# Kick_Sheet.net
KiCad netlist of a schematic drawn in Altium Designer
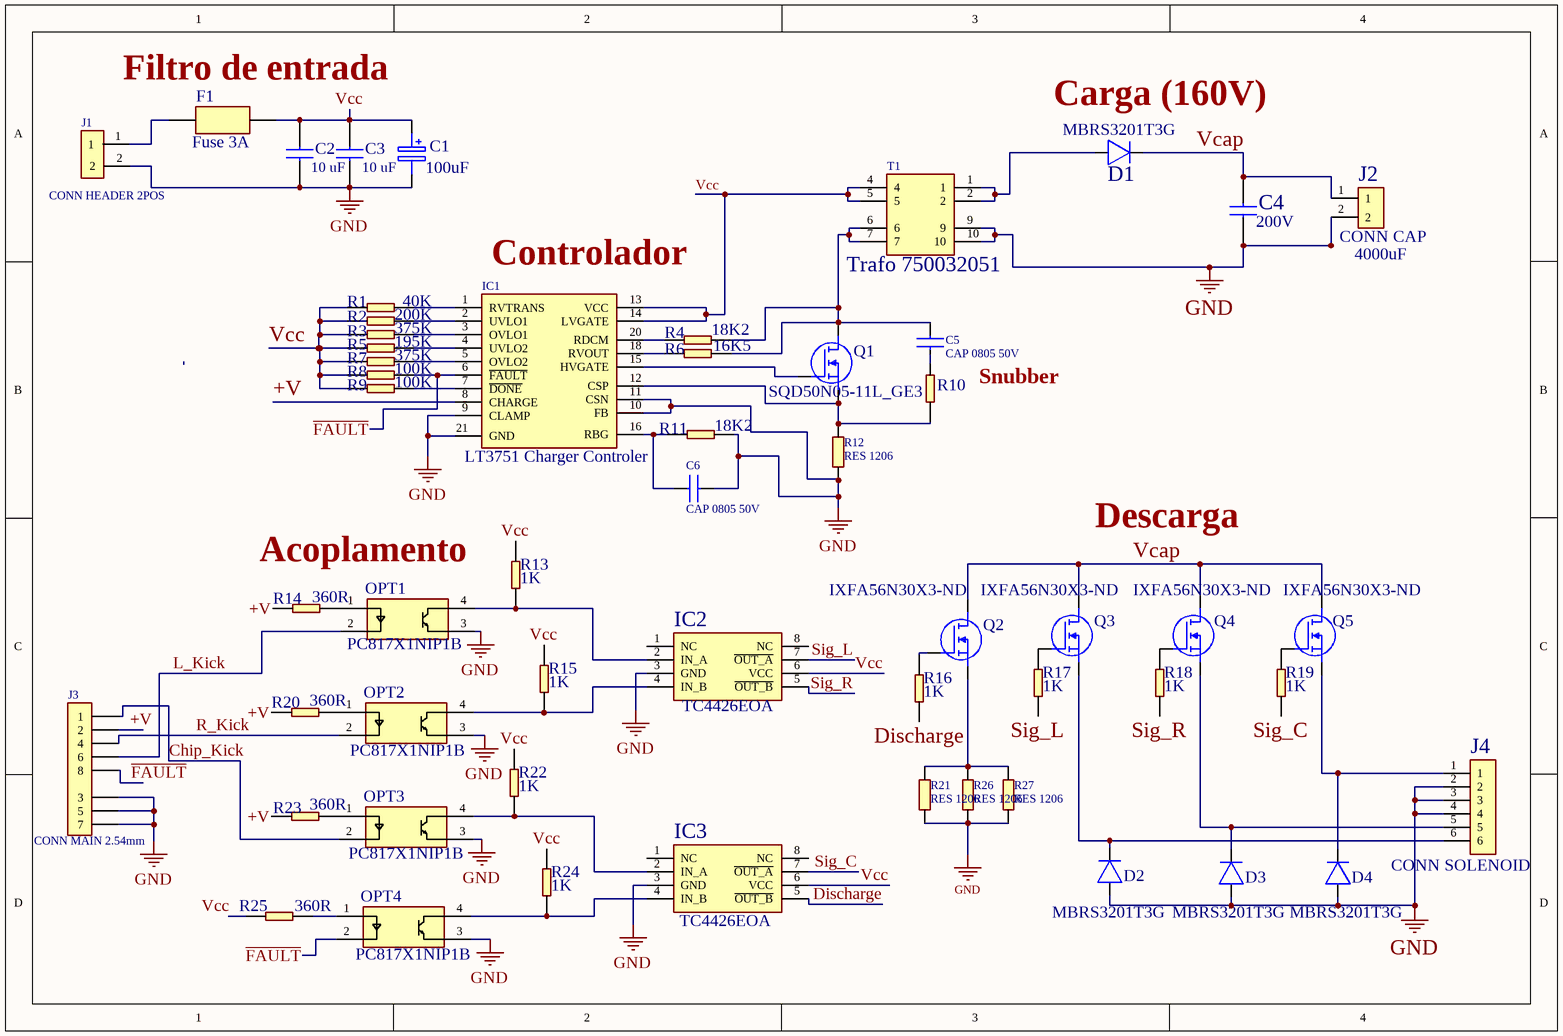
[diagram p0: Kick_Sheet.SchDoc]

(export (version "E")
  (design (tool "Eeschema 10.0.6"))
  (components
    (comp (ref "C1")
      (value "100uF")
      (footprint "SamacSys:CAPAE830X1050N")
      (fields
        (field (name "MANUFACTURER_PART_NUMBER") "UCD1H101MNL1GS")
        (field (name "MOUSER PART NUMBER") "647-UCD1H101MNL1GS")
        (field (name "RS PART NUMBER") "7151372P")
      )
      (libsource (lib "LIB_SCH_Kick") (part "CAP ALUM 100UF 20% 50V SMD"))
    )
    (comp (ref "C2")
      (value "10 uF")
      (footprint "PcbLib1:CAPCER1206")
      (description "Capacitor C3216C0G1H103J060AA")
      (fields
        (field (name "MANUFACTURER_PART_NUMBER") "C3216C0G1H103J060AA")
        (field (name "MOUSER PART NUMBER") "810-C3216C0G1H103J-1")
      )
      (libsource (lib "Schlib1") (part "CAP CER 1206"))
    )
    (comp (ref "C3")
      (value "10 uF")
      (footprint "PcbLib1:CAPCER1206")
      (description "Capacitor C3216C0G1H103J060AA")
      (fields
        (field (name "MANUFACTURER_PART_NUMBER") "C3216C0G1H103J060AA")
        (field (name "MOUSER PART NUMBER") "810-C3216C0G1H103J-1")
      )
      (libsource (lib "Schlib1") (part "CAP CER 1206"))
    )
    (comp (ref "C4")
      (value "200V")
      (footprint "PcbLib1:CAP OUT 2225")
      (description "Capacitor\r\nCAP CER 1UF 200V X7R 2225\r\n720-1136-1-ND\r\nVJ2225Y105KXCAT")
      (fields
        (field (name "MANUFACTURER_PART_NUMBER") "2225HC103KAZ1A")
        (field (name "MOUSER PART NUMBER") "581-2225HC103KAZ1A")
      )
      (libsource (lib "Schlib1") (part "CAP OUT 2225"))
    )
    (comp (ref "C5")
      (value "CAP 0805 50V")
      (footprint "LIB_PCB_Kick:CAP0805 50v")
      (description "Capacitor\r\n08055A101JAT2A")
      (fields
        (field (name "MANUFACTURER_PART_NUMBER") "08055A101JAT2A")
        (field (name "MOUSER PART NUMBER") "581-08055A101J")
      )
      (libsource (lib "LIB_SCH_Kick") (part "CAP 0805 50V"))
    )
    (comp (ref "C6")
      (value "CAP 0805 50V")
      (footprint "LIB_PCB_Kick:CAP0805 50v")
      (description "Capacitor\r\n08055A101JAT2A")
      (fields
        (field (name "MANUFACTURER_PART_NUMBER") "08055A101JAT2A")
        (field (name "MOUSER PART NUMBER") "581-08055A101J")
      )
      (libsource (lib "LIB_SCH_Kick") (part "CAP 0805 50V"))
    )
    (comp (ref "D1")
      (value "MBRS3201T3G")
      (footprint "PcbLib1:DIODE MBRS3201T")
      (description "Diode\r\nMBRS3201T3G")
      (fields
        (field (name "MOUSER PART NUMBER") "863-MBRS3201T3G")
        (field (name "RS PART NUMBER") "7925640P")
      )
      (libsource (lib "Schlib1") (part "DIODE MBRS3201T3G"))
    )
    (comp (ref "D2")
      (value "MBRS3201T3G")
      (footprint "PcbLib1:DIODE MBRS3201T")
      (description "Diode\r\nMBRS3201T3G")
      (fields
        (field (name "MOUSER PART NUMBER") "863-MBRS3201T3G")
        (field (name "RS PART NUMBER") "7925640P")
      )
      (libsource (lib "Schlib1") (part "DIODE MBRS3201T3G"))
    )
    (comp (ref "D3")
      (value "MBRS3201T3G")
      (footprint "PcbLib1:DIODE MBRS3201T")
      (description "Diode\r\nMBRS3201T3G")
      (fields
        (field (name "MOUSER PART NUMBER") "863-MBRS3201T3G")
        (field (name "RS PART NUMBER") "7925640P")
      )
      (libsource (lib "Schlib1") (part "DIODE MBRS3201T3G"))
    )
    (comp (ref "D4")
      (value "MBRS3201T3G")
      (footprint "PcbLib1:DIODE MBRS3201T")
      (description "Diode\r\nMBRS3201T3G")
      (fields
        (field (name "MOUSER PART NUMBER") "863-MBRS3201T3G")
        (field (name "RS PART NUMBER") "7925640P")
      )
      (libsource (lib "Schlib1") (part "DIODE MBRS3201T3G"))
    )
    (comp (ref "F1")
      (value "Fuse 3A")
      (footprint "PcbLib1:Fuse 3A 63V")
      (description "Fuse\r\nFUSE 3.0A 63VAC/DC SLOW 1206\r\n507-1896-1-ND\r\n0685T3000-01")
      (fields
        (field (name "MANUFACTURER_PART_NUMBER") "0466001.NRHF")
        (field (name "MOUSER PART NUMBER") "576-0466001.NRHF")
      )
      (libsource (lib "Schlib1") (part "Fuse 3A 63V"))
    )
    (comp (ref "IC1")
      (value "LT3751 Charger Controler")
      (footprint "PcbLib1:LT3751 Charger Controler")
      (description "Integrated Circuit")
      (fields (field (name "MANUFACTURER_PART_NUMBER") "LT3751EFEPBF"))
      (libsource (lib "Schlib1") (part "LT3751 Charger Controler"))
    )
    (comp (ref "IC2")
      (value "TC4426EOA")
      (footprint "PcbLib1:SOIC127_TC4426")
      (description "Integrated Circuit")
      (fields (field (name "MOUSER PART NUMBER") "579-TC4426EOA") (field (name "RS PART NUMBER") "6684345"))
      (libsource (lib "Schlib1") (part "TC4426EOA"))
    )
    (comp (ref "IC3")
      (value "TC4426EOA")
      (footprint "PcbLib1:SOIC127_TC4426")
      (description "Integrated Circuit")
      (fields (field (name "MOUSER PART NUMBER") "579-TC4426EOA") (field (name "RS PART NUMBER") "6684345"))
      (libsource (lib "Schlib1") (part "TC4426EOA"))
    )
    (comp (ref "J1")
      (value "CONN HEADER 2POS")
      (footprint "LIB_PCB_Kick:Battery Reto Connector")
      (description "CONN HEADER R/A 2POS 2.54MM\r\n22-05-3021\r\nWM4300-ND")
      (fields
        (field (name "MANUFACTURER_PART_NUMBER") "22-05-3021")
        (field (name "MOUSER PART NUMBER") "538-22-05-3021")
      )
      (libsource (lib "LIB_SCH_Kick") (part "Battery Connector"))
    )
    (comp (ref "J2")
      (value "CONN CAP")
      (footprint "PcbLib1:CONN CAP")
      (description "Connector\r\nCONN HEADER VERT 2POS 3.96MM\r\n0009652028\r\nWM18823-ND")
      (fields
        (field (name "MANUFACTURER_PART_NUMBER") "09-65-2028")
        (field (name "MOUSER PART NUMBER") "538-09-65-2028")
        (field (name "CAPACITANCIA") "4000uF")
      )
      (libsource (lib "Schlib1") (part "CONN CAP"))
    )
    (comp (ref "J3")
      (value "CONN MAIN 2.54mm")
      (footprint "LIB_PCB_Kick:CONN MAIN 2.54mm")
      (description "Connector\r\n\r\nCONN HEADER VERT 8POS 2.54MM\r\n\r\nM20-9980445\r\n\r\n952-2122-ND")
      (fields
        (field (name "MANUFACTURER_PART_NUMBER") "20021311-00010T4LF")
        (field (name "MOUSER PART NUMBER") "649-221311-00010T4LF")
      )
      (libsource (lib "LIB_SCH_Kick") (part "CONN MAIN 2.54mm"))
    )
    (comp (ref "J4")
      (value "CONN SOLENOID")
      (footprint "PcbLib1:CONN SOLENOID")
      (description "Connector\r\nCONN HEADER VERT 6POS 3.96MM\r\n0026604060\r\nWM4624-ND")
      (fields
        (field (name "MANUFACTURER_PART_NUMBER") "640445-6")
        (field (name "MOUSER PART NUMBER") "571-6404456")
      )
      (libsource (lib "Schlib1") (part "CONN SOLENOID"))
    )
    (comp (ref "OPT1")
      (value "PC817X1NIP1B")
      (footprint "PcbLib1:SOP254_Opto_PC817")
      (description "Integrated Circuit")
      (fields (field (name "MOUSER PART NUMBER") "852-PC817X1NIP1B"))
      (libsource (lib "Schlib1") (part "PC817X1NIP1B"))
    )
    (comp (ref "OPT2")
      (value "PC817X1NIP1B")
      (footprint "PcbLib1:SOP254_Opto_PC817")
      (description "Integrated Circuit")
      (fields (field (name "MOUSER PART NUMBER") "852-PC817X1NIP1B"))
      (libsource (lib "Schlib1") (part "PC817X1NIP1B"))
    )
    (comp (ref "OPT3")
      (value "PC817X1NIP1B")
      (footprint "PcbLib1:SOP254_Opto_PC817")
      (description "Integrated Circuit")
      (fields (field (name "MOUSER PART NUMBER") "852-PC817X1NIP1B"))
      (libsource (lib "Schlib1") (part "PC817X1NIP1B"))
    )
    (comp (ref "OPT4")
      (value "PC817X1NIP1B")
      (footprint "PcbLib1:SOP254_Opto_PC817")
      (description "Integrated Circuit")
      (fields (field (name "MOUSER PART NUMBER") "852-PC817X1NIP1B"))
      (libsource (lib "Schlib1") (part "PC817X1NIP1B"))
    )
    (comp (ref "Q1")
      (value "Mosfet N 50V 50A")
      (footprint "PcbLib1:Mosfet Chaveamento")
      (fields (field (name "MANUFACTURER_PART_NUMBER") "SQD50N05-11L_GE3"))
      (libsource (lib "Schlib1") (part "Mosfet Chaveamento"))
    )
    (comp (ref "Q2")
      (value "Mosfet N Disparo")
      (footprint "PcbLib1:Mosfet Disparo 2")
      (fields (field (name "MANUFACTURER_PART_NUMBER") "IXFA56N30X3-ND"))
      (libsource (lib "Schlib1") (part "Mosfet N Disparo"))
    )
    (comp (ref "Q3")
      (value "Mosfet N Disparo")
      (footprint "PcbLib1:Mosfet Disparo 2")
      (fields (field (name "MANUFACTURER_PART_NUMBER") "IXFA56N30X3-ND"))
      (libsource (lib "Schlib1") (part "Mosfet N Disparo"))
    )
    (comp (ref "Q4")
      (value "Mosfet N Disparo")
      (footprint "PcbLib1:Mosfet Disparo 2")
      (fields (field (name "MANUFACTURER_PART_NUMBER") "IXFA56N30X3-ND"))
      (libsource (lib "Schlib1") (part "Mosfet N Disparo"))
    )
    (comp (ref "Q5")
      (value "Mosfet N Disparo")
      (footprint "PcbLib1:Mosfet Disparo 2")
      (fields (field (name "MANUFACTURER_PART_NUMBER") "IXFA56N30X3-ND"))
      (libsource (lib "Schlib1") (part "Mosfet N Disparo"))
    )
    (comp (ref "R1")
      (value "40K")
      (footprint "PcbLib1:RES 0805")
      (description "Resistor 0805")
      (fields
        (field (name "MANUFACTURER_PART_NUMBER") "CPF0805B105RE1")
        (field (name "MOUSER PART NUMBER") "279-CPF0805B105RE1")
      )
      (libsource (lib "") (part "Resistor 0805_1"))
    )
    (comp (ref "R2")
      (value "200K")
      (footprint "PcbLib1:RES 0805")
      (description "Resistor 0805")
      (fields
        (field (name "MANUFACTURER_PART_NUMBER") "CPF0805B105RE1")
        (field (name "MOUSER PART NUMBER") "279-CPF0805B105RE1")
      )
      (libsource (lib "") (part "Resistor 0805_1"))
    )
    (comp (ref "R3")
      (value "375K")
      (footprint "PcbLib1:RES 0805")
      (description "Resistor 0805")
      (fields
        (field (name "MANUFACTURER_PART_NUMBER") "CPF0805B105RE1")
        (field (name "MOUSER PART NUMBER") "279-CPF0805B105RE1")
      )
      (libsource (lib "") (part "Resistor 0805_1"))
    )
    (comp (ref "R4")
      (value "18K2")
      (footprint "PcbLib1:RES 0805")
      (description "Resistor 0805")
      (fields
        (field (name "MANUFACTURER_PART_NUMBER") "CPF0805B105RE1")
        (field (name "MOUSER PART NUMBER") "279-CPF0805B105RE1")
      )
      (libsource (lib "") (part "Resistor 0805_1"))
    )
    (comp (ref "R5")
      (value "195K")
      (footprint "PcbLib1:RES 0805")
      (description "Resistor 0805")
      (fields
        (field (name "MANUFACTURER_PART_NUMBER") "CPF0805B105RE1")
        (field (name "MOUSER PART NUMBER") "279-CPF0805B105RE1")
      )
      (libsource (lib "") (part "Resistor 0805_1"))
    )
    (comp (ref "R6")
      (value "16K5")
      (footprint "PcbLib1:RES 0805")
      (description "Resistor 0805")
      (fields
        (field (name "MANUFACTURER_PART_NUMBER") "CPF0805B105RE1")
        (field (name "MOUSER PART NUMBER") "279-CPF0805B105RE1")
      )
      (libsource (lib "") (part "Resistor 0805_1"))
    )
    (comp (ref "R7")
      (value "375K")
      (footprint "PcbLib1:RES 0805")
      (description "Resistor 0805")
      (fields
        (field (name "MANUFACTURER_PART_NUMBER") "CPF0805B105RE1")
        (field (name "MOUSER PART NUMBER") "279-CPF0805B105RE1")
      )
      (libsource (lib "") (part "Resistor 0805_1"))
    )
    (comp (ref "R8")
      (value "100K")
      (footprint "PcbLib1:RES 0805")
      (description "Resistor 0805")
      (fields
        (field (name "MANUFACTURER_PART_NUMBER") "CPF0805B105RE1")
        (field (name "MOUSER PART NUMBER") "279-CPF0805B105RE1")
      )
      (libsource (lib "") (part "Resistor 0805_1"))
    )
    (comp (ref "R9")
      (value "100K")
      (footprint "PcbLib1:RES 0805")
      (description "Resistor 0805")
      (fields
        (field (name "MANUFACTURER_PART_NUMBER") "CPF0805B105RE1")
        (field (name "MOUSER PART NUMBER") "279-CPF0805B105RE1")
      )
      (libsource (lib "") (part "Resistor 0805_1"))
    )
    (comp (ref "R10")
      (value "~")
      (footprint "PcbLib1:RES 0805")
      (description "Resistor 0805")
      (fields
        (field (name "MANUFACTURER_PART_NUMBER") "CPF0805B105RE1")
        (field (name "MOUSER PART NUMBER") "279-CPF0805B105RE1")
      )
      (libsource (lib "Schlib1") (part "Resistor 0805"))
    )
    (comp (ref "R11")
      (value "18K2")
      (footprint "PcbLib1:RES 0805")
      (description "Resistor 0805")
      (fields
        (field (name "MANUFACTURER_PART_NUMBER") "CPF0805B105RE1")
        (field (name "MOUSER PART NUMBER") "279-CPF0805B105RE1")
      )
      (libsource (lib "") (part "Resistor 0805_1"))
    )
    (comp (ref "R12")
      (value "RES 1206")
      (footprint "LIB_PCB_Kick:Res 1206")
      (description "Resistor CR1206-FW-1504ELF")
      (fields
        (field (name "MANUFACTURER_PART_NUMBER") "CR1206-FW-1504ELF")
        (field (name "MOUSER PART NUMBER") "652-CR1206FW1504ELF")
      )
      (libsource (lib "") (part "RES 1206_1"))
    )
    (comp (ref "R13")
      (value "1K")
      (footprint "PcbLib1:RES 0805")
      (description "Resistor 0805")
      (fields
        (field (name "MANUFACTURER_PART_NUMBER") "CPF0805B105RE1")
        (field (name "MOUSER PART NUMBER") "279-CPF0805B105RE1")
      )
      (libsource (lib "Schlib1") (part "Resistor 0805"))
    )
    (comp (ref "R14")
      (value "360R")
      (footprint "PcbLib1:RES 0805")
      (description "Resistor 0805")
      (fields
        (field (name "MANUFACTURER_PART_NUMBER") "CPF0805B105RE1")
        (field (name "MOUSER PART NUMBER") "279-CPF0805B105RE1")
      )
      (libsource (lib "") (part "Resistor 0805_1"))
    )
    (comp (ref "R15")
      (value "1K")
      (footprint "PcbLib1:RES 0805")
      (description "Resistor 0805")
      (fields
        (field (name "MANUFACTURER_PART_NUMBER") "CPF0805B105RE1")
        (field (name "MOUSER PART NUMBER") "279-CPF0805B105RE1")
      )
      (libsource (lib "Schlib1") (part "Resistor 0805"))
    )
    (comp (ref "R16")
      (value "1K")
      (footprint "PcbLib1:RES 0805")
      (description "Resistor 0805")
      (fields
        (field (name "MANUFACTURER_PART_NUMBER") "CPF0805B105RE1")
        (field (name "MOUSER PART NUMBER") "279-CPF0805B105RE1")
      )
      (libsource (lib "Schlib1") (part "Resistor 0805"))
    )
    (comp (ref "R17")
      (value "1K")
      (footprint "PcbLib1:RES 0805")
      (description "Resistor 0805")
      (fields
        (field (name "MANUFACTURER_PART_NUMBER") "CPF0805B105RE1")
        (field (name "MOUSER PART NUMBER") "279-CPF0805B105RE1")
      )
      (libsource (lib "Schlib1") (part "Resistor 0805"))
    )
    (comp (ref "R18")
      (value "1K")
      (footprint "PcbLib1:RES 0805")
      (description "Resistor 0805")
      (fields
        (field (name "MANUFACTURER_PART_NUMBER") "CPF0805B105RE1")
        (field (name "MOUSER PART NUMBER") "279-CPF0805B105RE1")
      )
      (libsource (lib "Schlib1") (part "Resistor 0805"))
    )
    (comp (ref "R19")
      (value "1K")
      (footprint "PcbLib1:RES 0805")
      (description "Resistor 0805")
      (fields
        (field (name "MANUFACTURER_PART_NUMBER") "CPF0805B105RE1")
        (field (name "MOUSER PART NUMBER") "279-CPF0805B105RE1")
      )
      (libsource (lib "Schlib1") (part "Resistor 0805"))
    )
    (comp (ref "R20")
      (value "360R")
      (footprint "PcbLib1:RES 0805")
      (description "Resistor 0805")
      (fields
        (field (name "MANUFACTURER_PART_NUMBER") "CPF0805B105RE1")
        (field (name "MOUSER PART NUMBER") "279-CPF0805B105RE1")
      )
      (libsource (lib "") (part "Resistor 0805_1"))
    )
    (comp (ref "R21")
      (value "RES 1206")
      (footprint "LIB_PCB_Kick:Res 1206")
      (description "Resistor CR1206-FW-1504ELF")
      (fields
        (field (name "MANUFACTURER_PART_NUMBER") "CR1206-FW-1504ELF")
        (field (name "MOUSER PART NUMBER") "652-CR1206FW1504ELF")
      )
      (libsource (lib "LIB_SCH_Kick") (part "RES 1206"))
    )
    (comp (ref "R22")
      (value "1K")
      (footprint "PcbLib1:RES 0805")
      (description "Resistor 0805")
      (fields
        (field (name "MANUFACTURER_PART_NUMBER") "CPF0805B105RE1")
        (field (name "MOUSER PART NUMBER") "279-CPF0805B105RE1")
      )
      (libsource (lib "Schlib1") (part "Resistor 0805"))
    )
    (comp (ref "R23")
      (value "360R")
      (footprint "PcbLib1:RES 0805")
      (description "Resistor 0805")
      (fields
        (field (name "MANUFACTURER_PART_NUMBER") "CPF0805B105RE1")
        (field (name "MOUSER PART NUMBER") "279-CPF0805B105RE1")
      )
      (libsource (lib "") (part "Resistor 0805_1"))
    )
    (comp (ref "R24")
      (value "1K")
      (footprint "PcbLib1:RES 0805")
      (description "Resistor 0805")
      (fields
        (field (name "MANUFACTURER_PART_NUMBER") "CPF0805B105RE1")
        (field (name "MOUSER PART NUMBER") "279-CPF0805B105RE1")
      )
      (libsource (lib "Schlib1") (part "Resistor 0805"))
    )
    (comp (ref "R25")
      (value "360R")
      (footprint "LIB_PCB_Kick:RES 0805")
      (description "Resistor")
      (fields
        (field (name "MANUFACTURER_PART_NUMBER") "CPF0805B105RE1")
        (field (name "MOUSER PART NUMBER") "279-CPF0805B105RE1")
      )
      (libsource (lib "LIB_SCH_Kick") (part "Resistor 0805"))
    )
    (comp (ref "R26")
      (value "RES 1206")
      (footprint "LIB_PCB_Kick:Res 1206")
      (description "Resistor CR1206-FW-1504ELF")
      (fields
        (field (name "MANUFACTURER_PART_NUMBER") "CR1206-FW-1504ELF")
        (field (name "MOUSER PART NUMBER") "652-CR1206FW1504ELF")
      )
      (libsource (lib "LIB_SCH_Kick") (part "RES 1206"))
    )
    (comp (ref "R27")
      (value "RES 1206")
      (footprint "LIB_PCB_Kick:Res 1206")
      (description "Resistor CR1206-FW-1504ELF")
      (fields
        (field (name "MANUFACTURER_PART_NUMBER") "CR1206-FW-1504ELF")
        (field (name "MOUSER PART NUMBER") "652-CR1206FW1504ELF")
      )
      (libsource (lib "LIB_SCH_Kick") (part "RES 1206"))
    )
    (comp (ref "T1")
      (value "Trafo 750032051")
      (footprint "PcbLib1:Trafo Flyback")
      (description "Transformer")
      (fields (field (name "MANUFACTURER_PART_NUMBER") "750032051"))
      (libsource (lib "Schlib1") (part "Trafo 750032051"))
    )
  )
  (nets
    (net (code "1") (name "/+V") (class "Default")
      (node (ref "IC1") (pin "8") (pinfunction "CHARGE_8") (pintype "passive"))
      (node (ref "J3") (pin "2") (pinfunction "2_2") (pintype "passive"))
      (node (ref "R14") (pin "1") (pinfunction "1_1") (pintype "passive"))
      (node (ref "R20") (pin "1") (pinfunction "1_1") (pintype "passive"))
      (node (ref "R23") (pin "1") (pinfunction "1_1") (pintype "passive"))
    )
    (net (code "3") (name "/Chip_Kick") (class "Default")
      (node (ref "J3") (pin "1") (pinfunction "1_1") (pintype "passive"))
      (node (ref "OPT3") (pin "2") (pinfunction "CATHODE_2") (pintype "passive"))
    )
    (net (code "4") (name "/Discharge") (class "Default")
      (node (ref "IC3") (pin "5") (pinfunction "~{OUT_B}_5") (pintype "passive"))
      (node (ref "R16") (pin "1") (pinfunction "1_1") (pintype "passive"))
    )
    (net (code "5") (name "/L_Kick") (class "Default")
      (node (ref "J3") (pin "6") (pinfunction "6_6") (pintype "passive"))
      (node (ref "OPT1") (pin "2") (pinfunction "CATHODE_2") (pintype "passive"))
    )
    (net (code "6") (name "/R_Kick") (class "Default")
      (node (ref "J3") (pin "4") (pinfunction "4_4") (pintype "passive"))
      (node (ref "OPT2") (pin "2") (pinfunction "CATHODE_2") (pintype "passive"))
    )
    (net (code "7") (name "/Sig_C") (class "Default")
      (node (ref "IC3") (pin "7") (pinfunction "~{OUT_A}_7") (pintype "passive"))
      (node (ref "R19") (pin "1") (pinfunction "1_1") (pintype "passive"))
    )
    (net (code "8") (name "/Sig_L") (class "Default")
      (node (ref "IC2") (pin "7") (pinfunction "~{OUT_A}_7") (pintype "passive"))
      (node (ref "R17") (pin "1") (pinfunction "1_1") (pintype "passive"))
    )
    (net (code "9") (name "/Sig_R") (class "Default")
      (node (ref "IC2") (pin "5") (pinfunction "~{OUT_B}_5") (pintype "passive"))
      (node (ref "R18") (pin "1") (pinfunction "1_1") (pintype "passive"))
    )
    (net (code "10") (name "/Vcap") (class "Default")
      (node (ref "C4") (pin "2") (pinfunction "2_2") (pintype "passive"))
      (node (ref "D1") (pin "1") (pinfunction "K_1") (pintype "passive"))
      (node (ref "J2") (pin "1") (pinfunction "1_1") (pintype "passive"))
      (node (ref "Q2") (pin "2") (pinfunction "D_2") (pintype "passive"))
      (node (ref "Q3") (pin "2") (pinfunction "D_2") (pintype "passive"))
      (node (ref "Q4") (pin "2") (pinfunction "D_2") (pintype "passive"))
      (node (ref "Q5") (pin "2") (pinfunction "D_2") (pintype "passive"))
    )
    (net (code "11") (name "/Vcc") (class "Default")
      (node (ref "C1") (pin "1") (pinfunction "+_1") (pintype "passive"))
      (node (ref "C2") (pin "2") (pinfunction "2_2") (pintype "passive"))
      (node (ref "C3") (pin "2") (pinfunction "2_2") (pintype "passive"))
      (node (ref "F1") (pin "2") (pinfunction "2_2") (pintype "passive"))
      (node (ref "IC1") (pin "13") (pinfunction "VCC_13") (pintype "passive"))
      (node (ref "IC1") (pin "14") (pinfunction "LVGATE_14") (pintype "passive"))
      (node (ref "IC2") (pin "6") (pinfunction "VCC_6") (pintype "passive"))
      (node (ref "IC3") (pin "6") (pinfunction "VCC_6") (pintype "passive"))
      (node (ref "R1") (pin "1") (pinfunction "1_1") (pintype "passive"))
      (node (ref "R13") (pin "2") (pinfunction "2_2") (pintype "passive"))
      (node (ref "R15") (pin "2") (pinfunction "2_2") (pintype "passive"))
      (node (ref "R2") (pin "1") (pinfunction "1_1") (pintype "passive"))
      (node (ref "R22") (pin "2") (pinfunction "2_2") (pintype "passive"))
      (node (ref "R24") (pin "2") (pinfunction "2_2") (pintype "passive"))
      (node (ref "R25") (pin "1") (pinfunction "1_1") (pintype "passive"))
      (node (ref "R3") (pin "1") (pinfunction "1_1") (pintype "passive"))
      (node (ref "R5") (pin "1") (pinfunction "1_1") (pintype "passive"))
      (node (ref "R7") (pin "1") (pinfunction "1_1") (pintype "passive"))
      (node (ref "R8") (pin "1") (pinfunction "1_1") (pintype "passive"))
      (node (ref "R9") (pin "1") (pinfunction "1_1") (pintype "passive"))
      (node (ref "T1") (pin "4") (pinfunction "4_4") (pintype "passive"))
      (node (ref "T1") (pin "5") (pinfunction "5_5") (pintype "passive"))
    )
    (net (code "12") (name "/~{FAULT}") (class "Default")
      (node (ref "IC1") (pin "6") (pinfunction "~{FAULT}_6") (pintype "passive"))
      (node (ref "J3") (pin "8") (pinfunction "8_8") (pintype "passive"))
      (node (ref "OPT4") (pin "2") (pinfunction "CATHODE_2") (pintype "passive"))
      (node (ref "R8") (pin "2") (pinfunction "2_2") (pintype "passive"))
    )
    (net (code "13") (name "GND") (class "Default")
      (node (ref "C1") (pin "2") (pinfunction "-_2") (pintype "passive"))
      (node (ref "C2") (pin "1") (pinfunction "1_1") (pintype "passive"))
      (node (ref "C3") (pin "1") (pinfunction "1_1") (pintype "passive"))
      (node (ref "C4") (pin "1") (pinfunction "1_1") (pintype "passive"))
      (node (ref "C6") (pin "1") (pinfunction "1_1") (pintype "passive"))
      (node (ref "D2") (pin "2") (pinfunction "A_2") (pintype "passive"))
      (node (ref "D3") (pin "2") (pinfunction "A_2") (pintype "passive"))
      (node (ref "D4") (pin "2") (pinfunction "A_2") (pintype "passive"))
      (node (ref "IC1") (pin "10") (pinfunction "FB_10") (pintype "passive"))
      (node (ref "IC1") (pin "11") (pinfunction "CSN_11") (pintype "passive"))
      (node (ref "IC1") (pin "21") (pinfunction "GND_21") (pintype "passive"))
      (node (ref "IC1") (pin "9") (pinfunction "CLAMP_9") (pintype "passive"))
      (node (ref "IC2") (pin "3") (pinfunction "GND_3") (pintype "passive"))
      (node (ref "IC3") (pin "3") (pinfunction "GND_3") (pintype "passive"))
      (node (ref "J1") (pin "2") (pinfunction "2_2") (pintype "passive"))
      (node (ref "J2") (pin "2") (pinfunction "2_2") (pintype "passive"))
      (node (ref "J3") (pin "3") (pinfunction "3_3") (pintype "passive"))
      (node (ref "J3") (pin "5") (pinfunction "5_5") (pintype "passive"))
      (node (ref "J3") (pin "7") (pinfunction "7_7") (pintype "passive"))
      (node (ref "J4") (pin "2") (pinfunction "2_2") (pintype "passive"))
      (node (ref "J4") (pin "3") (pinfunction "3_3") (pintype "passive"))
      (node (ref "J4") (pin "4") (pinfunction "4_4") (pintype "passive"))
      (node (ref "OPT1") (pin "3") (pinfunction "EMITTER_3") (pintype "passive"))
      (node (ref "OPT2") (pin "3") (pinfunction "EMITTER_3") (pintype "passive"))
      (node (ref "OPT3") (pin "3") (pinfunction "EMITTER_3") (pintype "passive"))
      (node (ref "OPT4") (pin "3") (pinfunction "EMITTER_3") (pintype "passive"))
      (node (ref "R11") (pin "2") (pinfunction "2_2") (pintype "passive"))
      (node (ref "R12") (pin "2") (pinfunction "2_2") (pintype "passive"))
      (node (ref "R21") (pin "1") (pinfunction "1_1") (pintype "passive"))
      (node (ref "R26") (pin "1") (pinfunction "1_1") (pintype "passive"))
      (node (ref "R27") (pin "1") (pinfunction "1_1") (pintype "passive"))
      (node (ref "T1") (pin "10") (pinfunction "10_10") (pintype "passive"))
      (node (ref "T1") (pin "9") (pinfunction "9_9") (pintype "passive"))
    )
    (net (code "14") (name "Net-(C5-Pad1)") (class "Default")
      (node (ref "C5") (pin "1") (pinfunction "1_1") (pintype "passive"))
      (node (ref "R10") (pin "2") (pinfunction "2_2") (pintype "passive"))
    )
    (net (code "15") (name "Net-(D1-A)") (class "Default")
      (node (ref "D1") (pin "2") (pinfunction "A_2") (pintype "passive"))
      (node (ref "T1") (pin "1") (pinfunction "1_1") (pintype "passive"))
      (node (ref "T1") (pin "2") (pinfunction "2_2") (pintype "passive"))
    )
    (net (code "16") (name "Net-(D2-K)") (class "Default")
      (node (ref "D2") (pin "1") (pinfunction "K_1") (pintype "passive"))
      (node (ref "J4") (pin "6") (pinfunction "6_6") (pintype "passive"))
      (node (ref "Q3") (pin "3") (pinfunction "S_3") (pintype "passive"))
    )
    (net (code "17") (name "Net-(D3-K)") (class "Default")
      (node (ref "D3") (pin "1") (pinfunction "K_1") (pintype "passive"))
      (node (ref "J4") (pin "5") (pinfunction "5_5") (pintype "passive"))
      (node (ref "Q4") (pin "3") (pinfunction "S_3") (pintype "passive"))
    )
    (net (code "18") (name "Net-(D4-K)") (class "Default")
      (node (ref "D4") (pin "1") (pinfunction "K_1") (pintype "passive"))
      (node (ref "J4") (pin "1") (pinfunction "1_1") (pintype "passive"))
      (node (ref "Q5") (pin "3") (pinfunction "S_3") (pintype "passive"))
    )
    (net (code "19") (name "Net-(F1-Pad1)") (class "Default")
      (node (ref "F1") (pin "1") (pinfunction "1_1") (pintype "passive"))
      (node (ref "J1") (pin "1") (pinfunction "1_1") (pintype "passive"))
    )
    (net (code "20") (name "Net-(IC1-CSP)") (class "Default")
      (node (ref "IC1") (pin "12") (pinfunction "CSP_12") (pintype "passive"))
      (node (ref "Q1") (pin "3") (pinfunction "S_3") (pintype "passive"))
      (node (ref "R10") (pin "1") (pinfunction "1_1") (pintype "passive"))
      (node (ref "R12") (pin "1") (pinfunction "1_1") (pintype "passive"))
    )
    (net (code "21") (name "Net-(IC1-HVGATE)") (class "Default")
      (node (ref "IC1") (pin "15") (pinfunction "HVGATE_15") (pintype "passive"))
      (node (ref "Q1") (pin "1") (pinfunction "G_1") (pintype "passive"))
    )
    (net (code "22") (name "Net-(IC1-OVLO1)") (class "Default")
      (node (ref "IC1") (pin "3") (pinfunction "OVLO1_3") (pintype "passive"))
      (node (ref "R3") (pin "2") (pinfunction "2_2") (pintype "passive"))
    )
    (net (code "23") (name "Net-(IC1-OVLO2)") (class "Default")
      (node (ref "IC1") (pin "5") (pinfunction "OVLO2_5") (pintype "passive"))
      (node (ref "R7") (pin "2") (pinfunction "2_2") (pintype "passive"))
    )
    (net (code "24") (name "Net-(IC1-RBG)") (class "Default")
      (node (ref "C6") (pin "2") (pinfunction "2_2") (pintype "passive"))
      (node (ref "IC1") (pin "16") (pinfunction "RBG_16") (pintype "passive"))
      (node (ref "R11") (pin "1") (pinfunction "1_1") (pintype "passive"))
    )
    (net (code "25") (name "Net-(IC1-RDCM)") (class "Default")
      (node (ref "IC1") (pin "20") (pinfunction "RDCM_20") (pintype "passive"))
      (node (ref "R4") (pin "1") (pinfunction "1_1") (pintype "passive"))
    )
    (net (code "26") (name "Net-(IC1-RVOUT)") (class "Default")
      (node (ref "IC1") (pin "18") (pinfunction "RVOUT_18") (pintype "passive"))
      (node (ref "R6") (pin "1") (pinfunction "1_1") (pintype "passive"))
    )
    (net (code "27") (name "Net-(IC1-RVTRANS)") (class "Default")
      (node (ref "IC1") (pin "1") (pinfunction "RVTRANS_1") (pintype "passive"))
      (node (ref "R1") (pin "2") (pinfunction "2_2") (pintype "passive"))
    )
    (net (code "28") (name "Net-(IC1-UVLO1)") (class "Default")
      (node (ref "IC1") (pin "2") (pinfunction "UVLO1_2") (pintype "passive"))
      (node (ref "R2") (pin "2") (pinfunction "2_2") (pintype "passive"))
    )
    (net (code "29") (name "Net-(IC1-UVLO2)") (class "Default")
      (node (ref "IC1") (pin "4") (pinfunction "UVLO2_4") (pintype "passive"))
      (node (ref "R5") (pin "2") (pinfunction "2_2") (pintype "passive"))
    )
    (net (code "30") (name "Net-(IC1-~{DONE})") (class "Default")
      (node (ref "IC1") (pin "7") (pinfunction "~{DONE}_7") (pintype "passive"))
      (node (ref "R9") (pin "2") (pinfunction "2_2") (pintype "passive"))
    )
    (net (code "31") (name "Net-(IC2-IN_A)") (class "Default")
      (node (ref "IC2") (pin "2") (pinfunction "IN_A_2") (pintype "passive"))
      (node (ref "OPT1") (pin "4") (pinfunction "COLLECTOR_4") (pintype "passive"))
      (node (ref "R13") (pin "1") (pinfunction "1_1") (pintype "passive"))
    )
    (net (code "32") (name "Net-(IC2-IN_B)") (class "Default")
      (node (ref "IC2") (pin "4") (pinfunction "IN_B_4") (pintype "passive"))
      (node (ref "OPT2") (pin "4") (pinfunction "COLLECTOR_4") (pintype "passive"))
      (node (ref "R15") (pin "1") (pinfunction "1_1") (pintype "passive"))
    )
    (net (code "33") (name "Net-(IC3-IN_A)") (class "Default")
      (node (ref "IC3") (pin "2") (pinfunction "IN_A_2") (pintype "passive"))
      (node (ref "OPT3") (pin "4") (pinfunction "COLLECTOR_4") (pintype "passive"))
      (node (ref "R22") (pin "1") (pinfunction "1_1") (pintype "passive"))
    )
    (net (code "34") (name "Net-(IC3-IN_B)") (class "Default")
      (node (ref "IC3") (pin "4") (pinfunction "IN_B_4") (pintype "passive"))
      (node (ref "OPT4") (pin "4") (pinfunction "COLLECTOR_4") (pintype "passive"))
      (node (ref "R24") (pin "1") (pinfunction "1_1") (pintype "passive"))
    )
    (net (code "35") (name "Net-(OPT1-ANODE)") (class "Default")
      (node (ref "OPT1") (pin "1") (pinfunction "ANODE_1") (pintype "passive"))
      (node (ref "R14") (pin "2") (pinfunction "2_2") (pintype "passive"))
    )
    (net (code "36") (name "Net-(OPT2-ANODE)") (class "Default")
      (node (ref "OPT2") (pin "1") (pinfunction "ANODE_1") (pintype "passive"))
      (node (ref "R20") (pin "2") (pinfunction "2_2") (pintype "passive"))
    )
    (net (code "37") (name "Net-(OPT3-ANODE)") (class "Default")
      (node (ref "OPT3") (pin "1") (pinfunction "ANODE_1") (pintype "passive"))
      (node (ref "R23") (pin "2") (pinfunction "2_2") (pintype "passive"))
    )
    (net (code "38") (name "Net-(OPT4-ANODE)") (class "Default")
      (node (ref "OPT4") (pin "1") (pinfunction "ANODE_1") (pintype "passive"))
      (node (ref "R25") (pin "2") (pinfunction "2_2") (pintype "passive"))
    )
    (net (code "39") (name "Net-(Q1-D)") (class "Default")
      (node (ref "C5") (pin "2") (pinfunction "2_2") (pintype "passive"))
      (node (ref "Q1") (pin "2") (pinfunction "D_2") (pintype "passive"))
      (node (ref "R4") (pin "2") (pinfunction "2_2") (pintype "passive"))
      (node (ref "R6") (pin "2") (pinfunction "2_2") (pintype "passive"))
      (node (ref "T1") (pin "6") (pinfunction "6_6") (pintype "passive"))
      (node (ref "T1") (pin "7") (pinfunction "7_7") (pintype "passive"))
    )
    (net (code "40") (name "Net-(Q2-G)") (class "Default")
      (node (ref "Q2") (pin "1") (pinfunction "G_1") (pintype "passive"))
      (node (ref "R16") (pin "2") (pinfunction "2_2") (pintype "passive"))
    )
    (net (code "41") (name "Net-(Q2-S)") (class "Default")
      (node (ref "Q2") (pin "3") (pinfunction "S_3") (pintype "passive"))
      (node (ref "R21") (pin "2") (pinfunction "2_2") (pintype "passive"))
      (node (ref "R26") (pin "2") (pinfunction "2_2") (pintype "passive"))
      (node (ref "R27") (pin "2") (pinfunction "2_2") (pintype "passive"))
    )
    (net (code "42") (name "Net-(Q3-G)") (class "Default")
      (node (ref "Q3") (pin "1") (pinfunction "G_1") (pintype "passive"))
      (node (ref "R17") (pin "2") (pinfunction "2_2") (pintype "passive"))
    )
    (net (code "43") (name "Net-(Q4-G)") (class "Default")
      (node (ref "Q4") (pin "1") (pinfunction "G_1") (pintype "passive"))
      (node (ref "R18") (pin "2") (pinfunction "2_2") (pintype "passive"))
    )
    (net (code "44") (name "Net-(Q5-G)") (class "Default")
      (node (ref "Q5") (pin "1") (pinfunction "G_1") (pintype "passive"))
      (node (ref "R19") (pin "2") (pinfunction "2_2") (pintype "passive"))
    )
    (net (code "45") (name "unconnected-(IC1-NC-Pad17)") (class "Default")
      (node (ref "IC1") (pin "17") (pinfunction "NC_17") (pintype "passive"))
    )
    (net (code "46") (name "unconnected-(IC1-NC-Pad19)") (class "Default")
      (node (ref "IC1") (pin "19") (pinfunction "NC_19") (pintype "passive"))
    )
    (net (code "47") (name "unconnected-(IC2-NC-Pad1)") (class "Default")
      (node (ref "IC2") (pin "1") (pinfunction "NC_1") (pintype "passive"))
    )
    (net (code "48") (name "unconnected-(IC2-NC-Pad8)") (class "Default")
      (node (ref "IC2") (pin "8") (pinfunction "NC_8") (pintype "passive"))
    )
    (net (code "49") (name "unconnected-(IC3-NC-Pad1)") (class "Default")
      (node (ref "IC3") (pin "1") (pinfunction "NC_1") (pintype "passive"))
    )
    (net (code "50") (name "unconnected-(IC3-NC-Pad8)") (class "Default")
      (node (ref "IC3") (pin "8") (pinfunction "NC_8") (pintype "passive"))
    )
    (net (code "51") (name "unconnected-(T1-Pad3)") (class "Default")
      (node (ref "T1") (pin "3") (pinfunction "3_3") (pintype "passive"))
    )
    (net (code "52") (name "unconnected-(T1-Pad8)") (class "Default")
      (node (ref "T1") (pin "8") (pinfunction "8_8") (pintype "passive"))
    )
  )
)
